# Copy_of_User_Interface.net
KiCad netlist of a schematic drawn in Altium Designer
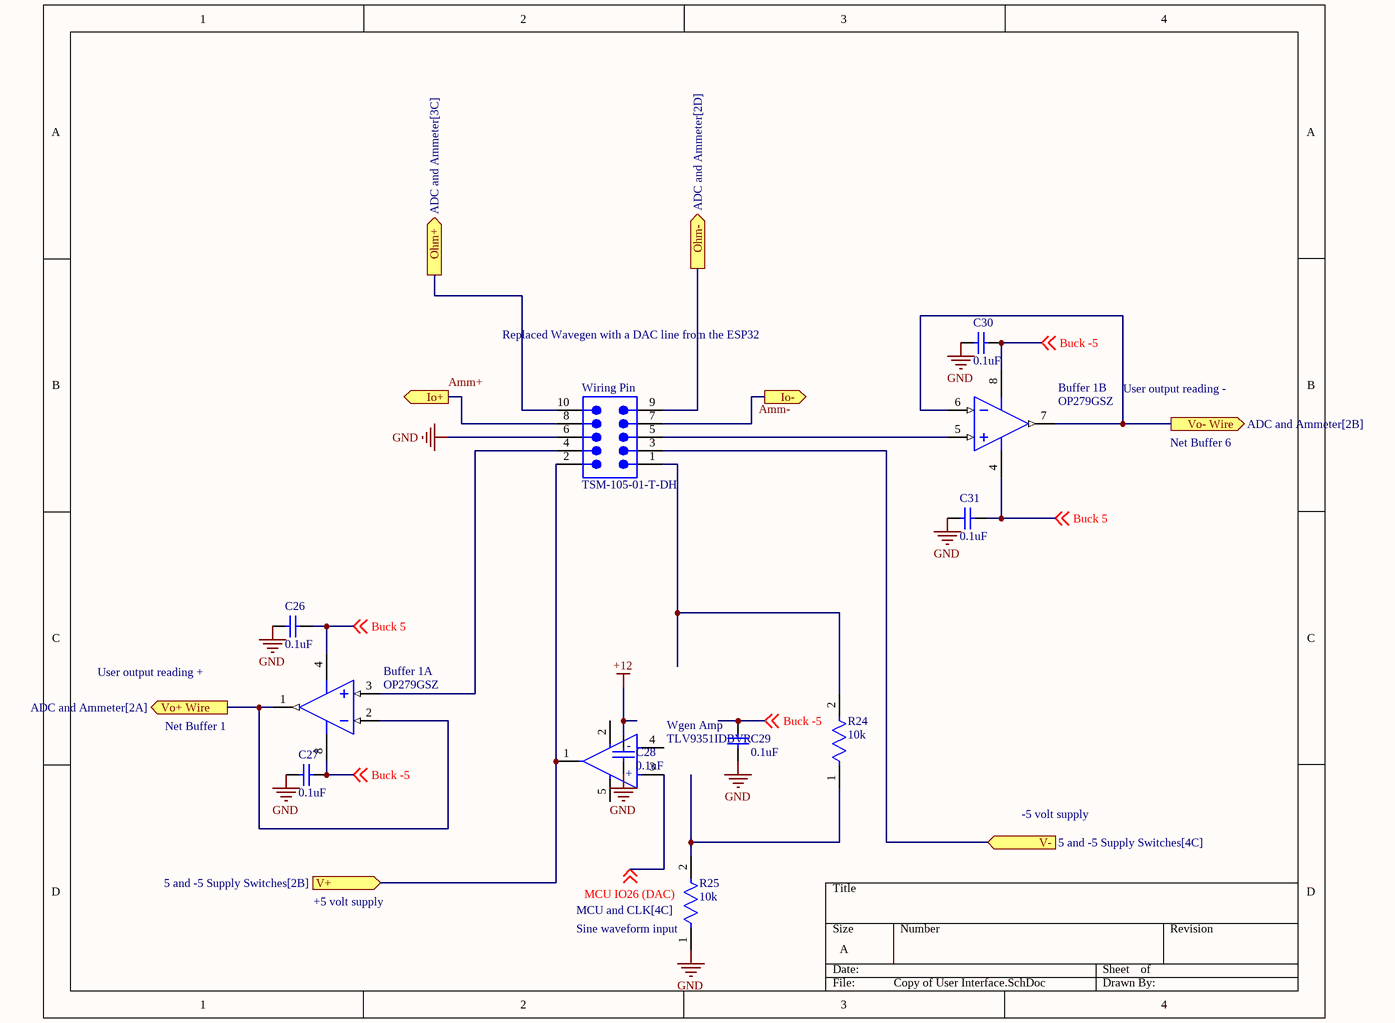
[diagram p0: Copy of User Interface.SchDoc]

(export (version "E")
  (design (tool "Eeschema 10.0.6"))
  (components
    (comp (ref "Buffer 1")
      (value "OP279GSZ")
      (footprint "ADI-R-8_N")
      (fields (field (name "MANUFACTURER") "Analog Devices") (field (name "GENERIC PART NUMBER") "OP279"))
      (libsource (lib "Altium Content Vault") (part "ADI-OP29X-R-8"))
    )
    (comp (ref "C26")
      (value "0.1uF")
      (footprint "CAPC2013X94X50LL20T25")
      (fields
        (field (name "PART NUMBER") "08055C104JAT4A")
        (field (name "MANUFACTURER") "AVX Interconnect / Elco")
      )
      (libsource (lib "Altium Content Vault") (part "CAP"))
    )
    (comp (ref "C27")
      (value "0.1uF")
      (footprint "CAPC2013X94X50LL20T25")
      (fields
        (field (name "PART NUMBER") "08055C104JAT4A")
        (field (name "MANUFACTURER") "AVX Interconnect / Elco")
      )
      (libsource (lib "Altium Content Vault") (part "CAP"))
    )
    (comp (ref "C28")
      (value "0.1uF")
      (footprint "CAPC2013X94X50LL20T25")
      (fields
        (field (name "PART NUMBER") "08055C104JAT4A")
        (field (name "MANUFACTURER") "AVX Interconnect / Elco")
      )
      (libsource (lib "Altium Content Vault") (part "CAP"))
    )
    (comp (ref "C29")
      (value "0.1uF")
      (footprint "CAPC2013X94X50LL20T25")
      (fields
        (field (name "PART NUMBER") "08055C104JAT4A")
        (field (name "MANUFACTURER") "AVX Interconnect / Elco")
      )
      (libsource (lib "Altium Content Vault") (part "CAP"))
    )
    (comp (ref "C30")
      (value "0.1uF")
      (footprint "CAPC2013X94X50LL20T25")
      (fields
        (field (name "PART NUMBER") "08055C104JAT4A")
        (field (name "MANUFACTURER") "AVX Interconnect / Elco")
      )
      (libsource (lib "Altium Content Vault") (part "CAP"))
    )
    (comp (ref "C31")
      (value "0.1uF")
      (footprint "CAPC2013X94X50LL20T25")
      (fields
        (field (name "PART NUMBER") "08055C104JAT4A")
        (field (name "MANUFACTURER") "AVX Interconnect / Elco")
      )
      (libsource (lib "Altium Content Vault") (part "CAP"))
    )
    (comp (ref "R24")
      (value "10k")
      (footprint "FP-RK73H1J-IPC_B")
      (description "10kΩ ±1% 0.1W Chip Resistor 0603 Thick Film AEC-Q200 Qualified")
      (fields (field (name "TOLERANCE") "1%"))
      (libsource (lib "Altium Content Vault") (part "1029c3af85768c4190bb7ad29bc67b5"))
    )
    (comp (ref "R25")
      (value "10k")
      (footprint "FP-RK73H1J-IPC_B")
      (description "10kΩ ±1% 0.1W Chip Resistor 0603 Thick Film AEC-Q200 Qualified")
      (fields (field (name "TOLERANCE") "1%"))
      (libsource (lib "Altium Content Vault") (part "1029c3af85768c4190bb7ad29bc67b5"))
    )
    (comp (ref "Wgen Amp")
      (value "TLV9351IDBVR")
      (footprint "FP-DBV0005A-IPC_C")
      (description "OPAMP")
      (libsource (lib "Altium Content Vault") (part "303ad2592cc7899f5e1082e1d8e7095"))
    )
    (comp (ref "Wiring Pin")
      (value "TSM-105-01-T-DH")
      (footprint "SMTC-TSM-105-01-X-DH")
      (fields (field (name "MANUFACTURER") "Samtec"))
      (libsource (lib "Altium Content Vault") (part "SMTC-TSM-105-01-X-X"))
    )
  )
  (nets
    (net (code "1") (name "+12") (class "Default")
      (node (ref "C28") (pin "2") (pinfunction "2_2") (pintype "passive"))
    )
    (net (code "4") (name "/Io+") (class "Default")
      (node (ref "Wiring Pin") (pin "8") (pinfunction "8_8") (pintype "passive"))
    )
    (net (code "5") (name "/Io-") (class "Default")
      (node (ref "Wiring Pin") (pin "7") (pinfunction "7_7") (pintype "passive"))
    )
    (net (code "6") (name "/Ohm+") (class "Default")
      (node (ref "Wiring Pin") (pin "10") (pinfunction "10_10") (pintype "passive"))
    )
    (net (code "7") (name "/Ohm-") (class "Default")
      (node (ref "Wiring Pin") (pin "9") (pinfunction "9_9") (pintype "passive"))
    )
    (net (code "8") (name "/V+") (class "Default")
      (node (ref "Wgen Amp") (pin "1") (pinfunction "OUT_1") (pintype "passive"))
      (node (ref "Wiring Pin") (pin "2") (pinfunction "2_2") (pintype "passive"))
    )
    (net (code "9") (name "/V-") (class "Default")
      (node (ref "Wiring Pin") (pin "3") (pinfunction "3_3") (pintype "passive"))
    )
    (net (code "10") (name "/Vo+ Wire") (class "Default")
      (node (ref "Buffer 1") (pin "1") (pinfunction "OUT_A_1") (pintype "output"))
      (node (ref "Buffer 1") (pin "2") (pinfunction "-IN_A_2") (pintype "input"))
    )
    (net (code "11") (name "/Vo- Wire") (class "Default")
      (node (ref "Buffer 1") (pin "6") (pinfunction "-IN_B_6") (pintype "input"))
      (node (ref "Buffer 1") (pin "7") (pinfunction "OUT_B_7") (pintype "output"))
    )
    (net (code "12") (name "Buck -5") (class "Default")
      (node (ref "Buffer 1") (pin "8") (pinfunction "+V_8") (pintype "power_in"))
      (node (ref "C27") (pin "2") (pinfunction "2_2") (pintype "passive"))
      (node (ref "C29") (pin "2") (pinfunction "2_2") (pintype "passive"))
      (node (ref "C30") (pin "2") (pinfunction "2_2") (pintype "passive"))
    )
    (net (code "13") (name "Buck 5") (class "Default")
      (node (ref "Buffer 1") (pin "4") (pinfunction "-V_4") (pintype "power_in"))
      (node (ref "C26") (pin "2") (pinfunction "2_2") (pintype "passive"))
      (node (ref "C31") (pin "2") (pinfunction "2_2") (pintype "passive"))
    )
    (net (code "14") (name "GND") (class "Default")
      (node (ref "C26") (pin "1") (pinfunction "1_1") (pintype "passive"))
      (node (ref "C27") (pin "1") (pinfunction "1_1") (pintype "passive"))
      (node (ref "C28") (pin "1") (pinfunction "1_1") (pintype "passive"))
      (node (ref "C29") (pin "1") (pinfunction "1_1") (pintype "passive"))
      (node (ref "C30") (pin "1") (pinfunction "1_1") (pintype "passive"))
      (node (ref "C31") (pin "1") (pinfunction "1_1") (pintype "passive"))
      (node (ref "R25") (pin "1") (pinfunction "1_1") (pintype "passive"))
      (node (ref "Wiring Pin") (pin "6") (pinfunction "6_6") (pintype "passive"))
    )
    (net (code "15") (name "MCU IO26 (DAC)") (class "Default")
      (node (ref "Wgen Amp") (pin "3") (pinfunction "IN+_3") (pintype "tri_state"))
    )
    (net (code "16") (name "Net-(Buffer 1A-+IN_A)") (class "Default")
      (node (ref "Buffer 1") (pin "3") (pinfunction "+IN_A_3") (pintype "input"))
      (node (ref "Wiring Pin") (pin "4") (pinfunction "4_4") (pintype "passive"))
    )
    (net (code "17") (name "Net-(Buffer 1B-+IN_B)") (class "Default")
      (node (ref "Buffer 1") (pin "5") (pinfunction "+IN_B_5") (pintype "input"))
      (node (ref "Wiring Pin") (pin "5") (pinfunction "5_5") (pintype "passive"))
    )
    (net (code "18") (name "Net-(R24-Pad1)") (class "Default")
      (node (ref "R24") (pin "1") (pinfunction "1_1") (pintype "passive"))
      (node (ref "R25") (pin "2") (pinfunction "2_2") (pintype "passive"))
    )
    (net (code "19") (name "Net-(R24-Pad2)") (class "Default")
      (node (ref "R24") (pin "2") (pinfunction "2_2") (pintype "passive"))
      (node (ref "Wiring Pin") (pin "1") (pinfunction "1_1") (pintype "passive"))
    )
    (net (code "20") (name "unconnected-(Wgen Amp-IN--Pad4)") (class "Default")
      (node (ref "Wgen Amp") (pin "4") (pinfunction "IN-_4") (pintype "tri_state"))
    )
    (net (code "21") (name "unconnected-(Wgen Amp-V+-Pad5)") (class "Default")
      (node (ref "Wgen Amp") (pin "5") (pinfunction "V+_5") (pintype "power_in"))
    )
    (net (code "22") (name "unconnected-(Wgen Amp-V--Pad2)") (class "Default")
      (node (ref "Wgen Amp") (pin "2") (pinfunction "V-_2") (pintype "power_in"))
    )
  )
)
